# LCD.net
KiCad netlist of a schematic drawn in Altium Designer
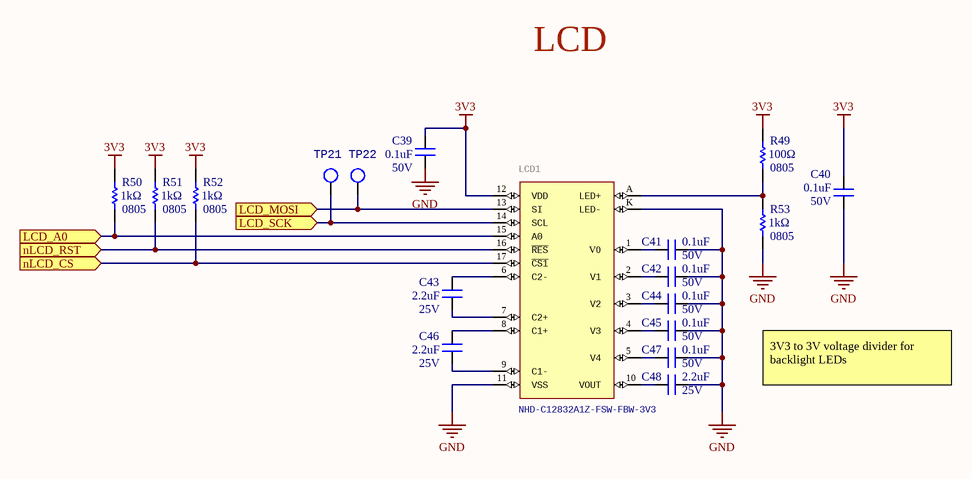
[diagram p0: LCD.SchDoc]

(export (version "E")
  (design (tool "Eeschema 10.0.6"))
  (components
    (comp (ref "C39")
      (value "0.1uF")
      (footprint "CAPC2012X140N")
      (description "CAP CER 0.1UF 50V X7R 0805")
      (fields
        (field (name "TOLERANCE") "10%")
        (field (name "VOLTAGE RATING") "50V")
        (field (name "Comment") "CAP_0.1uF_50V_0805")
      )
      (libsource (lib "UWRT_Schematic_Library_2020") (part "CAP_0.1uF_50V_0805"))
    )
    (comp (ref "C40")
      (value "0.1uF")
      (footprint "CAPC2012X140N")
      (description "CAP CER 0.1UF 50V X7R 0805")
      (fields
        (field (name "TOLERANCE") "10%")
        (field (name "VOLTAGE RATING") "50V")
        (field (name "Comment") "CAP_0.1uF_50V_0805")
      )
      (libsource (lib "UWRT_Schematic_Library_2020") (part "CAP_0.1uF_50V_0805"))
    )
    (comp (ref "C41")
      (value "0.1uF")
      (footprint "CAPC2012X140N")
      (description "CAP CER 0.1UF 50V X7R 0805")
      (fields
        (field (name "TOLERANCE") "10%")
        (field (name "VOLTAGE RATING") "50V")
        (field (name "Comment") "CAP_0.1uF_50V_0805")
      )
      (libsource (lib "UWRT_Schematic_Library_2020") (part "CAP_0.1uF_50V_0805"))
    )
    (comp (ref "C42")
      (value "0.1uF")
      (footprint "CAPC2012X140N")
      (description "CAP CER 0.1UF 50V X7R 0805")
      (fields
        (field (name "TOLERANCE") "10%")
        (field (name "VOLTAGE RATING") "50V")
        (field (name "Comment") "CAP_0.1uF_50V_0805")
      )
      (libsource (lib "UWRT_Schematic_Library_2020") (part "CAP_0.1uF_50V_0805"))
    )
    (comp (ref "C43")
      (value "2.2uF")
      (footprint "CAPC2012X140N")
      (description "CAP CER 2.2UF 25V X7R 0805")
      (fields
        (field (name "TOLERANCE") "10%")
        (field (name "VOLTAGE RATING") "25V")
        (field (name "Comment") "CAP_2.2uF_25V_0805")
      )
      (libsource (lib "UWRT_Schematic_Library_2020") (part "CAP_2.2uF_25V_0805"))
    )
    (comp (ref "C44")
      (value "0.1uF")
      (footprint "CAPC2012X140N")
      (description "CAP CER 0.1UF 50V X7R 0805")
      (fields
        (field (name "TOLERANCE") "10%")
        (field (name "VOLTAGE RATING") "50V")
        (field (name "Comment") "CAP_0.1uF_50V_0805")
      )
      (libsource (lib "UWRT_Schematic_Library_2020") (part "CAP_0.1uF_50V_0805"))
    )
    (comp (ref "C45")
      (value "0.1uF")
      (footprint "CAPC2012X140N")
      (description "CAP CER 0.1UF 50V X7R 0805")
      (fields
        (field (name "TOLERANCE") "10%")
        (field (name "VOLTAGE RATING") "50V")
        (field (name "Comment") "CAP_0.1uF_50V_0805")
      )
      (libsource (lib "UWRT_Schematic_Library_2020") (part "CAP_0.1uF_50V_0805"))
    )
    (comp (ref "C46")
      (value "2.2uF")
      (footprint "CAPC2012X140N")
      (description "CAP CER 2.2UF 25V X7R 0805")
      (fields
        (field (name "TOLERANCE") "10%")
        (field (name "VOLTAGE RATING") "25V")
        (field (name "Comment") "CAP_2.2uF_25V_0805")
      )
      (libsource (lib "UWRT_Schematic_Library_2020") (part "CAP_2.2uF_25V_0805"))
    )
    (comp (ref "C47")
      (value "0.1uF")
      (footprint "CAPC2012X140N")
      (description "CAP CER 0.1UF 50V X7R 0805")
      (fields
        (field (name "TOLERANCE") "10%")
        (field (name "VOLTAGE RATING") "50V")
        (field (name "Comment") "CAP_0.1uF_50V_0805")
      )
      (libsource (lib "UWRT_Schematic_Library_2020") (part "CAP_0.1uF_50V_0805"))
    )
    (comp (ref "C48")
      (value "2.2uF")
      (footprint "CAPC2012X140N")
      (description "CAP CER 2.2UF 25V X7R 0805")
      (fields
        (field (name "TOLERANCE") "10%")
        (field (name "VOLTAGE RATING") "25V")
        (field (name "Comment") "CAP_2.2uF_25V_0805")
      )
      (libsource (lib "UWRT_Schematic_Library_2020") (part "CAP_2.2uF_25V_0805"))
    )
    (comp (ref "LCD1")
      (value "NHD-C12832A1Z-FSW-FBW-3V3")
      (footprint "NHDC12832A1ZFSWFBW3V3")
      (description "LCD COG GRAPHIC 128X32")
      (libsource (lib "UWRT_Schematic_Library_2020") (part "NHD-C12832A1Z-FSW-FBW-3V3"))
    )
    (comp (ref "R49")
      (value "100Ω")
      (footprint "RESC2012X60N")
      (description "RES SMD 100 OHM 1% 1/8W 0805")
      (fields (field (name "CASE CODE (IMPERIAL)") "0805") (field (name "Comment") "RES_100Ω_0805"))
      (libsource (lib "UWRT_Schematic_Library_2020") (part "RES_100Ω_0805"))
    )
    (comp (ref "R50")
      (value "1kΩ")
      (footprint "RESC2012X60N")
      (description "RES SMD 1K OHM 1% 1/8W 0805")
      (fields
        (field (name "CASE CODE (IMPERIAL)") "0805")
        (field (name "TOLERANCE") "1%")
        (field (name "Comment") "RES_1kΩ_0805")
      )
      (libsource (lib "UWRT_Schematic_Library_2020") (part "RES_1kΩ_0805"))
    )
    (comp (ref "R51")
      (value "1kΩ")
      (footprint "RESC2012X60N")
      (description "RES SMD 1K OHM 1% 1/8W 0805")
      (fields
        (field (name "CASE CODE (IMPERIAL)") "0805")
        (field (name "TOLERANCE") "1%")
        (field (name "Comment") "RES_1kΩ_0805")
      )
      (libsource (lib "UWRT_Schematic_Library_2020") (part "RES_1kΩ_0805"))
    )
    (comp (ref "R52")
      (value "1kΩ")
      (footprint "RESC2012X60N")
      (description "RES SMD 1K OHM 1% 1/8W 0805")
      (fields
        (field (name "CASE CODE (IMPERIAL)") "0805")
        (field (name "TOLERANCE") "1%")
        (field (name "Comment") "RES_1kΩ_0805")
      )
      (libsource (lib "UWRT_Schematic_Library_2020") (part "RES_1kΩ_0805"))
    )
    (comp (ref "R53")
      (value "1kΩ")
      (footprint "RESC2012X60N")
      (description "RES SMD 1K OHM 1% 1/8W 0805")
      (fields
        (field (name "CASE CODE (IMPERIAL)") "0805")
        (field (name "TOLERANCE") "1%")
        (field (name "Comment") "RES_1kΩ_0805")
      )
      (libsource (lib "UWRT_Schematic_Library_2020") (part "RES_1kΩ_0805"))
    )
    (comp (ref "TP21")
      (value "TESTPOINT_LOOP")
      (footprint "TESTPOINT_LOOP")
      (description "Loop testpoint through-hole pad")
      (libsource (lib "UWRT_Schematic_Library_2020") (part "TESTPOINT_LOOP"))
    )
    (comp (ref "TP22")
      (value "TESTPOINT_LOOP")
      (footprint "TESTPOINT_LOOP")
      (description "Loop testpoint through-hole pad")
      (libsource (lib "UWRT_Schematic_Library_2020") (part "TESTPOINT_LOOP"))
    )
  )
  (nets
    (net (code "1") (name "/LCD_A0") (class "Default")
      (node (ref "LCD1") (pin "15") (pinfunction "A0_15") (pintype "bidirectional"))
      (node (ref "R50") (pin "1") (pinfunction "1_1") (pintype "passive"))
    )
    (net (code "2") (name "/LCD_MOSI") (class "Default")
      (node (ref "LCD1") (pin "13") (pinfunction "SI_13") (pintype "bidirectional"))
      (node (ref "TP22") (pin "1") (pintype "passive"))
    )
    (net (code "3") (name "/LCD_SCK") (class "Default")
      (node (ref "LCD1") (pin "14") (pinfunction "SCL_14") (pintype "bidirectional"))
      (node (ref "TP21") (pin "1") (pintype "passive"))
    )
    (net (code "4") (name "/nLCD_CS") (class "Default")
      (node (ref "LCD1") (pin "17") (pinfunction "~{CS1}_17") (pintype "bidirectional"))
      (node (ref "R52") (pin "1") (pinfunction "1_1") (pintype "passive"))
    )
    (net (code "5") (name "/nLCD_RST") (class "Default")
      (node (ref "LCD1") (pin "16") (pinfunction "~{RES}_16") (pintype "bidirectional"))
      (node (ref "R51") (pin "1") (pinfunction "1_1") (pintype "passive"))
    )
    (net (code "6") (name "3V3") (class "Default")
      (node (ref "C39") (pin "1") (pinfunction "1_1") (pintype "passive"))
      (node (ref "C40") (pin "1") (pinfunction "1_1") (pintype "passive"))
      (node (ref "LCD1") (pin "12") (pinfunction "VDD_12") (pintype "bidirectional"))
      (node (ref "R49") (pin "2") (pinfunction "2_2") (pintype "passive"))
      (node (ref "R50") (pin "2") (pinfunction "2_2") (pintype "passive"))
      (node (ref "R51") (pin "2") (pinfunction "2_2") (pintype "passive"))
      (node (ref "R52") (pin "2") (pinfunction "2_2") (pintype "passive"))
    )
    (net (code "7") (name "GND") (class "Default")
      (node (ref "C39") (pin "2") (pinfunction "2_2") (pintype "passive"))
      (node (ref "C40") (pin "2") (pinfunction "2_2") (pintype "passive"))
      (node (ref "C41") (pin "1") (pinfunction "1_1") (pintype "passive"))
      (node (ref "C42") (pin "1") (pinfunction "1_1") (pintype "passive"))
      (node (ref "C44") (pin "1") (pinfunction "1_1") (pintype "passive"))
      (node (ref "C45") (pin "1") (pinfunction "1_1") (pintype "passive"))
      (node (ref "C47") (pin "1") (pinfunction "1_1") (pintype "passive"))
      (node (ref "C48") (pin "1") (pinfunction "1_1") (pintype "passive"))
      (node (ref "LCD1") (pin "11") (pinfunction "VSS_11") (pintype "bidirectional"))
      (node (ref "LCD1") (pin "K") (pinfunction "LED-_K") (pintype "bidirectional"))
      (node (ref "R53") (pin "1") (pinfunction "1_1") (pintype "passive"))
    )
    (net (code "8") (name "Net-(LCD1-C1+)") (class "Default")
      (node (ref "C46") (pin "2") (pinfunction "2_2") (pintype "passive"))
      (node (ref "LCD1") (pin "8") (pinfunction "C1+_8") (pintype "bidirectional"))
    )
    (net (code "9") (name "Net-(LCD1-C1-)") (class "Default")
      (node (ref "C46") (pin "1") (pinfunction "1_1") (pintype "passive"))
      (node (ref "LCD1") (pin "9") (pinfunction "C1-_9") (pintype "bidirectional"))
    )
    (net (code "10") (name "Net-(LCD1-C2+)") (class "Default")
      (node (ref "C43") (pin "1") (pinfunction "1_1") (pintype "passive"))
      (node (ref "LCD1") (pin "7") (pinfunction "C2+_7") (pintype "bidirectional"))
    )
    (net (code "11") (name "Net-(LCD1-C2-)") (class "Default")
      (node (ref "C43") (pin "2") (pinfunction "2_2") (pintype "passive"))
      (node (ref "LCD1") (pin "6") (pinfunction "C2-_6") (pintype "bidirectional"))
    )
    (net (code "12") (name "Net-(LCD1-LED+)") (class "Default")
      (node (ref "LCD1") (pin "A") (pinfunction "LED+_A") (pintype "bidirectional"))
      (node (ref "R49") (pin "1") (pinfunction "1_1") (pintype "passive"))
      (node (ref "R53") (pin "2") (pinfunction "2_2") (pintype "passive"))
    )
    (net (code "13") (name "Net-(LCD1-V0)") (class "Default")
      (node (ref "C41") (pin "2") (pinfunction "2_2") (pintype "passive"))
      (node (ref "LCD1") (pin "1") (pinfunction "V0_1") (pintype "bidirectional"))
    )
    (net (code "14") (name "Net-(LCD1-V1)") (class "Default")
      (node (ref "C42") (pin "2") (pinfunction "2_2") (pintype "passive"))
      (node (ref "LCD1") (pin "2") (pinfunction "V1_2") (pintype "bidirectional"))
    )
    (net (code "15") (name "Net-(LCD1-V2)") (class "Default")
      (node (ref "C44") (pin "2") (pinfunction "2_2") (pintype "passive"))
      (node (ref "LCD1") (pin "3") (pinfunction "V2_3") (pintype "bidirectional"))
    )
    (net (code "16") (name "Net-(LCD1-V3)") (class "Default")
      (node (ref "C45") (pin "2") (pinfunction "2_2") (pintype "passive"))
      (node (ref "LCD1") (pin "4") (pinfunction "V3_4") (pintype "bidirectional"))
    )
    (net (code "17") (name "Net-(LCD1-V4)") (class "Default")
      (node (ref "C47") (pin "2") (pinfunction "2_2") (pintype "passive"))
      (node (ref "LCD1") (pin "5") (pinfunction "V4_5") (pintype "bidirectional"))
    )
    (net (code "18") (name "Net-(LCD1-VOUT)") (class "Default")
      (node (ref "C48") (pin "2") (pinfunction "2_2") (pintype "passive"))
      (node (ref "LCD1") (pin "10") (pinfunction "VOUT_10") (pintype "bidirectional"))
    )
  )
)
